# S03.net
KiCad netlist of a schematic drawn in Altium Designer
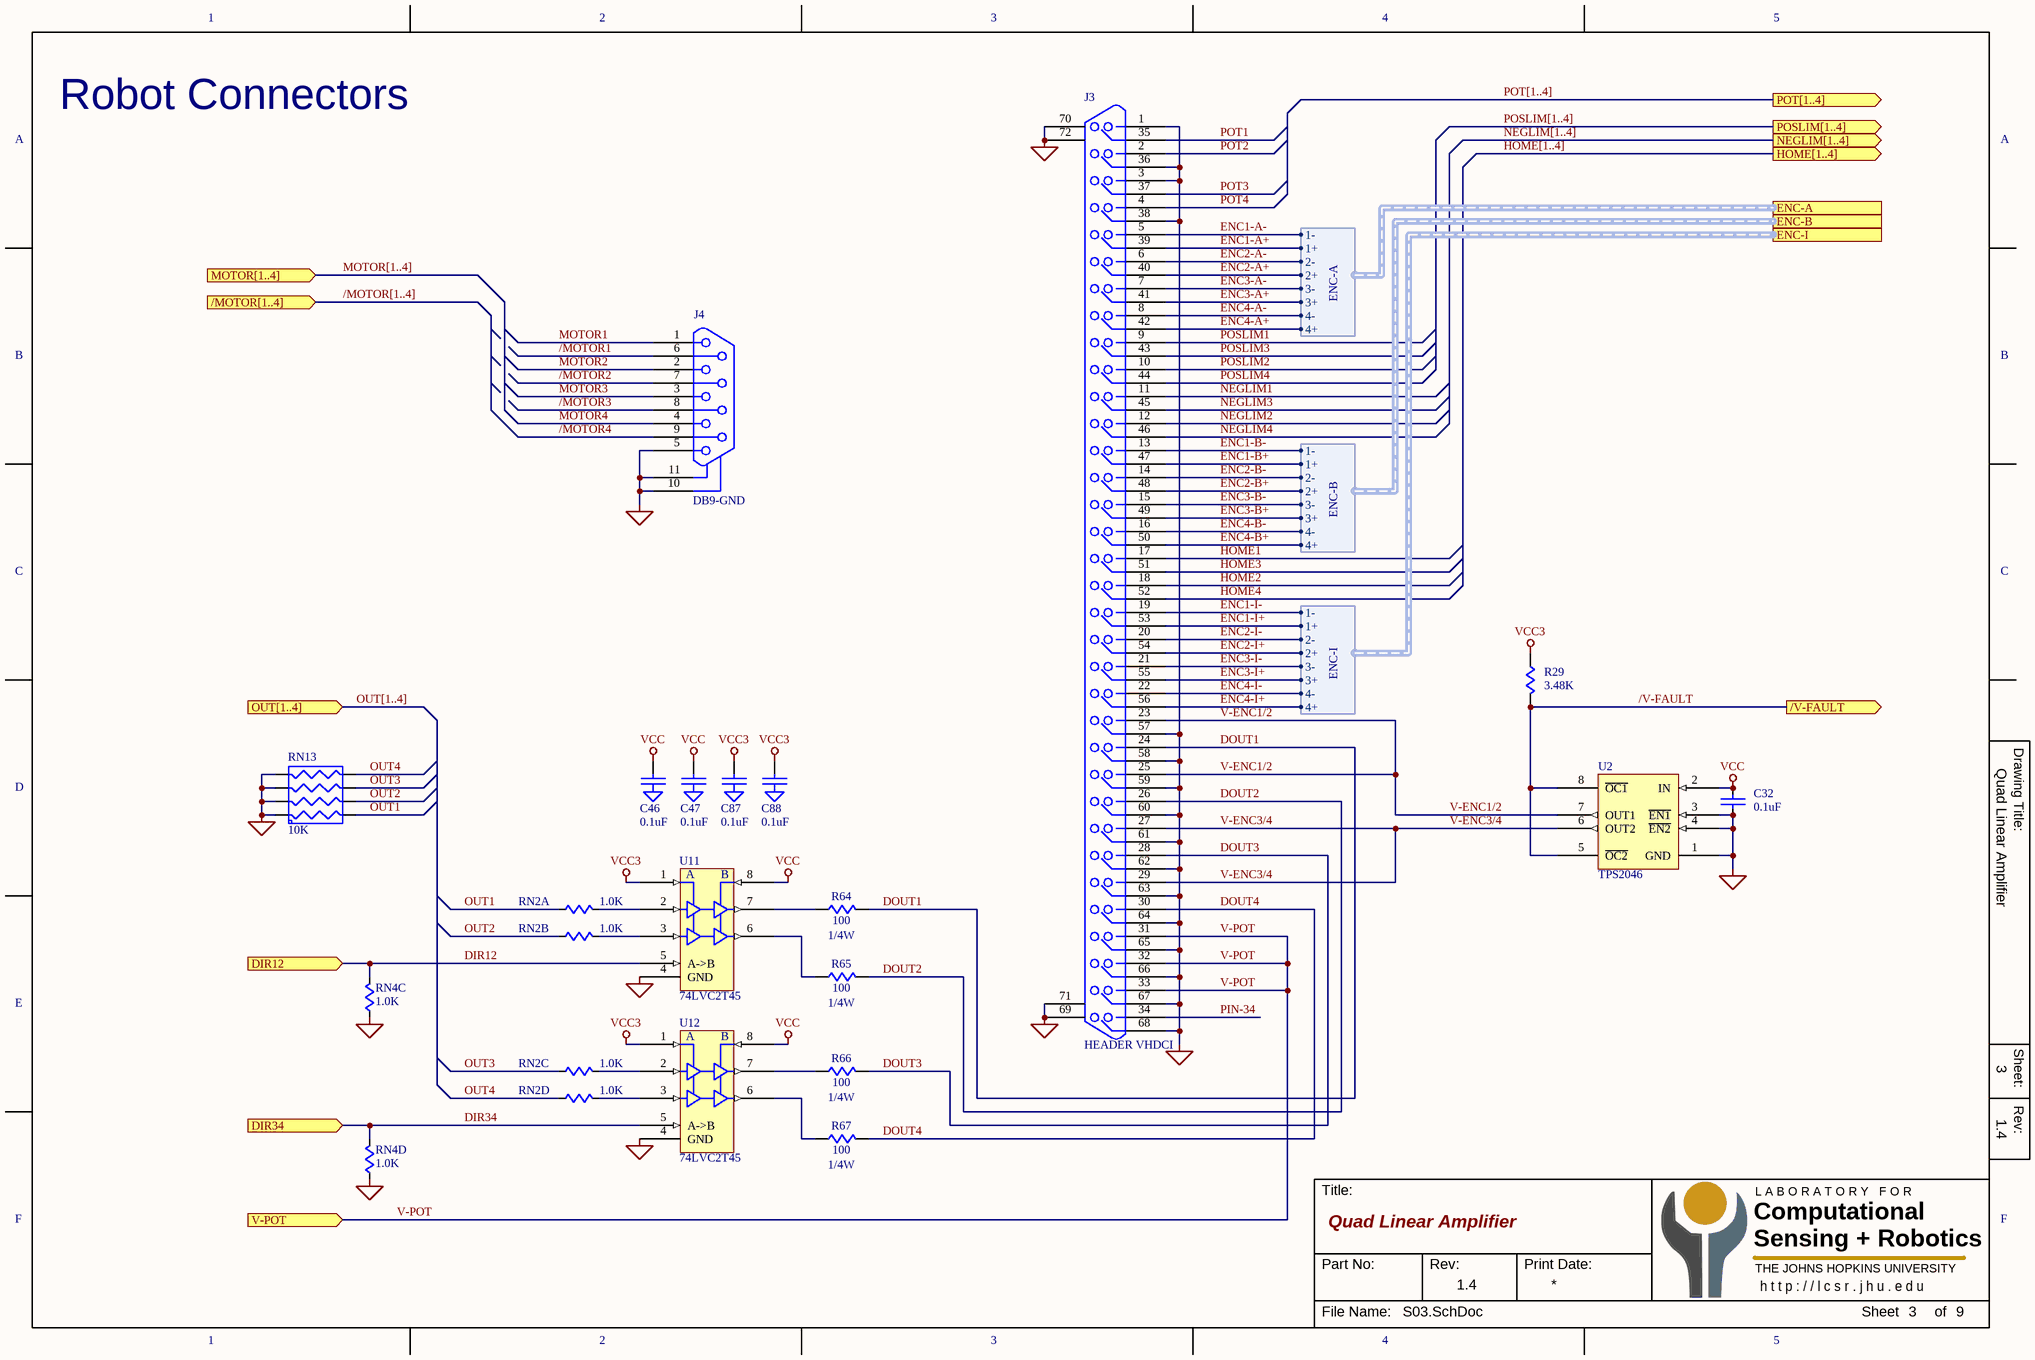
[diagram p0: S03.SchDoc]

(export (version "E")
  (design (tool "Eeschema 10.0.6"))
  (components
    (comp (ref "C32") (value "0.1uF") (footprint "C0603") (libsource (lib "LibJHU") (part "CAP-MINI")))
    (comp (ref "C46") (value "0.1uF") (footprint "C0603") (libsource (lib "LibJHU") (part "CAP-GND")))
    (comp (ref "C47") (value "0.1uF") (footprint "C0603") (libsource (lib "LibJHU") (part "CAP-GND")))
    (comp (ref "C87") (value "0.1uF") (footprint "C0603") (libsource (lib "LibJHU") (part "CAP-GND")))
    (comp (ref "C88") (value "0.1uF") (footprint "C0603") (libsource (lib "LibJHU") (part "CAP-GND")))
    (comp (ref "J3")
      (value "HEADER VHDCI")
      (footprint "CONN-VHDCI")
      (description "Molex Part #71430-0008")
      (libsource (lib "LibJHU") (part "HEADER VHDCI"))
    )
    (comp (ref "J4")
      (value "DB9-GND")
      (footprint "DB9F/RA-545-HDP")
      (libsource (lib "LibJHU") (part "DB9-GND"))
    )
    (comp (ref "R29") (value "3.48K") (footprint "R0603") (libsource (lib "LibJHU") (part "R")))
    (comp (ref "R64")
      (value "100")
      (footprint "R1206")
      (fields (field (name "ALTIUM_UNNAMED_1") "1/4W"))
      (libsource (lib "LibJHU") (part "R"))
    )
    (comp (ref "R65")
      (value "100")
      (footprint "R1206")
      (fields (field (name "ALTIUM_UNNAMED_1") "1/4W"))
      (libsource (lib "LibJHU") (part "R"))
    )
    (comp (ref "R66")
      (value "100")
      (footprint "R1206")
      (fields (field (name "ALTIUM_UNNAMED_1") "1/4W"))
      (libsource (lib "LibJHU") (part "R"))
    )
    (comp (ref "R67")
      (value "100")
      (footprint "R1206")
      (fields (field (name "ALTIUM_UNNAMED_1") "1/4W"))
      (libsource (lib "LibJHU") (part "R"))
    )
    (comp (ref "RN2")
      (value "1.0K")
      (footprint "RN-742C083")
      (libsource (lib "LibJHU") (part "RN-DISC-SM-4X"))
    )
    (comp (ref "RN4")
      (value "1.0K")
      (footprint "RN-742C083")
      (libsource (lib "LibJHU") (part "RN-DISC-SM-4X"))
    )
    (comp (ref "RN13")
      (value "10K")
      (footprint "RN-742C083")
      (libsource (lib "LibJHU") (part "RN-DISC-SM-4"))
    )
    (comp (ref "U2") (value "TPS2046") (footprint "SO-8") (libsource (lib "LibJHU") (part "TPS2046")))
    (comp (ref "U11") (value "74LVC2T45") (footprint "US8-8") (libsource (lib "LibJHU") (part "74LVC2T45")))
    (comp (ref "U12") (value "74LVC2T45") (footprint "US8-8") (libsource (lib "LibJHU") (part "74LVC2T45")))
  )
  (nets
    (net (code "8") (name "/DIR12") (class "Default")
      (node (ref "RN4") (pin "6") (pinfunction "6_6") (pintype "passive"))
      (node (ref "U11") (pin "5") (pinfunction "A->B_5") (pintype "input"))
    )
    (net (code "9") (name "/DIR34") (class "Default")
      (node (ref "RN4") (pin "5") (pinfunction "5_5") (pintype "passive"))
      (node (ref "U12") (pin "5") (pinfunction "A->B_5") (pintype "input"))
    )
    (net (code "10") (name "/DOUT1") (class "Default")
      (node (ref "J3") (pin "24") (pinfunction "24_24") (pintype "passive"))
      (node (ref "R64") (pin "2") (pinfunction "2_2") (pintype "passive"))
    )
    (net (code "11") (name "/DOUT2") (class "Default")
      (node (ref "J3") (pin "26") (pinfunction "26_26") (pintype "passive"))
      (node (ref "R65") (pin "2") (pinfunction "2_2") (pintype "passive"))
    )
    (net (code "12") (name "/DOUT3") (class "Default")
      (node (ref "J3") (pin "28") (pinfunction "28_28") (pintype "passive"))
      (node (ref "R66") (pin "2") (pinfunction "2_2") (pintype "passive"))
    )
    (net (code "13") (name "/DOUT4") (class "Default")
      (node (ref "J3") (pin "30") (pinfunction "30_30") (pintype "passive"))
      (node (ref "R67") (pin "2") (pinfunction "2_2") (pintype "passive"))
    )
    (net (code "14") (name "/ENC1-A+") (class "Default")
      (node (ref "J3") (pin "39") (pinfunction "39_39") (pintype "passive"))
    )
    (net (code "15") (name "/ENC1-A-") (class "Default")
      (node (ref "J3") (pin "5") (pinfunction "5_5") (pintype "passive"))
    )
    (net (code "16") (name "/ENC1-B+") (class "Default")
      (node (ref "J3") (pin "47") (pinfunction "47_47") (pintype "passive"))
    )
    (net (code "17") (name "/ENC1-B-") (class "Default")
      (node (ref "J3") (pin "13") (pinfunction "13_13") (pintype "passive"))
    )
    (net (code "18") (name "/ENC1-I+") (class "Default")
      (node (ref "J3") (pin "53") (pinfunction "53_53") (pintype "passive"))
    )
    (net (code "19") (name "/ENC1-I-") (class "Default")
      (node (ref "J3") (pin "19") (pinfunction "19_19") (pintype "passive"))
    )
    (net (code "20") (name "/ENC2-A+") (class "Default")
      (node (ref "J3") (pin "40") (pinfunction "40_40") (pintype "passive"))
    )
    (net (code "21") (name "/ENC2-A-") (class "Default")
      (node (ref "J3") (pin "6") (pinfunction "6_6") (pintype "passive"))
    )
    (net (code "22") (name "/ENC2-B+") (class "Default")
      (node (ref "J3") (pin "48") (pinfunction "48_48") (pintype "passive"))
    )
    (net (code "23") (name "/ENC2-B-") (class "Default")
      (node (ref "J3") (pin "14") (pinfunction "14_14") (pintype "passive"))
    )
    (net (code "24") (name "/ENC2-I+") (class "Default")
      (node (ref "J3") (pin "54") (pinfunction "54_54") (pintype "passive"))
    )
    (net (code "25") (name "/ENC2-I-") (class "Default")
      (node (ref "J3") (pin "20") (pinfunction "20_20") (pintype "passive"))
    )
    (net (code "26") (name "/ENC3-A+") (class "Default")
      (node (ref "J3") (pin "41") (pinfunction "41_41") (pintype "passive"))
    )
    (net (code "27") (name "/ENC3-A-") (class "Default")
      (node (ref "J3") (pin "7") (pinfunction "7_7") (pintype "passive"))
    )
    (net (code "28") (name "/ENC3-B+") (class "Default")
      (node (ref "J3") (pin "49") (pinfunction "49_49") (pintype "passive"))
    )
    (net (code "29") (name "/ENC3-B-") (class "Default")
      (node (ref "J3") (pin "15") (pinfunction "15_15") (pintype "passive"))
    )
    (net (code "30") (name "/ENC3-I+") (class "Default")
      (node (ref "J3") (pin "55") (pinfunction "55_55") (pintype "passive"))
    )
    (net (code "31") (name "/ENC3-I-") (class "Default")
      (node (ref "J3") (pin "21") (pinfunction "21_21") (pintype "passive"))
    )
    (net (code "32") (name "/ENC4-A+") (class "Default")
      (node (ref "J3") (pin "42") (pinfunction "42_42") (pintype "passive"))
    )
    (net (code "33") (name "/ENC4-A-") (class "Default")
      (node (ref "J3") (pin "8") (pinfunction "8_8") (pintype "passive"))
    )
    (net (code "34") (name "/ENC4-B+") (class "Default")
      (node (ref "J3") (pin "50") (pinfunction "50_50") (pintype "passive"))
    )
    (net (code "35") (name "/ENC4-B-") (class "Default")
      (node (ref "J3") (pin "16") (pinfunction "16_16") (pintype "passive"))
    )
    (net (code "36") (name "/ENC4-I+") (class "Default")
      (node (ref "J3") (pin "56") (pinfunction "56_56") (pintype "passive"))
    )
    (net (code "37") (name "/ENC4-I-") (class "Default")
      (node (ref "J3") (pin "22") (pinfunction "22_22") (pintype "passive"))
    )
    (net (code "38") (name "/HOME1") (class "Default")
      (node (ref "J3") (pin "17") (pinfunction "17_17") (pintype "passive"))
    )
    (net (code "39") (name "/HOME2") (class "Default")
      (node (ref "J3") (pin "18") (pinfunction "18_18") (pintype "passive"))
    )
    (net (code "40") (name "/HOME3") (class "Default")
      (node (ref "J3") (pin "51") (pinfunction "51_51") (pintype "passive"))
    )
    (net (code "41") (name "/HOME4") (class "Default")
      (node (ref "J3") (pin "52") (pinfunction "52_52") (pintype "passive"))
    )
    (net (code "43") (name "/MOTOR1") (class "Default") (node (ref "J4") (pin "1") (pintype "passive")))
    (net (code "44") (name "/MOTOR2") (class "Default") (node (ref "J4") (pin "2") (pintype "passive")))
    (net (code "45") (name "/MOTOR3") (class "Default") (node (ref "J4") (pin "3") (pintype "passive")))
    (net (code "46") (name "/MOTOR4") (class "Default") (node (ref "J4") (pin "4") (pintype "passive")))
    (net (code "48") (name "/NEGLIM1") (class "Default")
      (node (ref "J3") (pin "11") (pinfunction "11_11") (pintype "passive"))
    )
    (net (code "49") (name "/NEGLIM2") (class "Default")
      (node (ref "J3") (pin "12") (pinfunction "12_12") (pintype "passive"))
    )
    (net (code "50") (name "/NEGLIM3") (class "Default")
      (node (ref "J3") (pin "45") (pinfunction "45_45") (pintype "passive"))
    )
    (net (code "51") (name "/NEGLIM4") (class "Default")
      (node (ref "J3") (pin "46") (pinfunction "46_46") (pintype "passive"))
    )
    (net (code "53") (name "/OUT1") (class "Default")
      (node (ref "RN13") (pin "8") (pinfunction "R1.2_8") (pintype "passive"))
      (node (ref "RN2") (pin "1") (pinfunction "1_1") (pintype "passive"))
    )
    (net (code "54") (name "/OUT2") (class "Default")
      (node (ref "RN13") (pin "7") (pinfunction "R2.2_7") (pintype "passive"))
      (node (ref "RN2") (pin "2") (pinfunction "2_2") (pintype "passive"))
    )
    (net (code "55") (name "/OUT3") (class "Default")
      (node (ref "RN13") (pin "6") (pinfunction "R3.2_6") (pintype "passive"))
      (node (ref "RN2") (pin "3") (pinfunction "3_3") (pintype "passive"))
    )
    (net (code "56") (name "/OUT4") (class "Default")
      (node (ref "RN13") (pin "5") (pinfunction "R4.2_5") (pintype "passive"))
      (node (ref "RN2") (pin "4") (pinfunction "4_4") (pintype "passive"))
    )
    (net (code "58") (name "/PIN-34") (class "Default")
      (node (ref "J3") (pin "34") (pinfunction "34_34") (pintype "passive"))
    )
    (net (code "59") (name "/POSLIM1") (class "Default")
      (node (ref "J3") (pin "9") (pinfunction "9_9") (pintype "passive"))
    )
    (net (code "60") (name "/POSLIM2") (class "Default")
      (node (ref "J3") (pin "10") (pinfunction "10_10") (pintype "passive"))
    )
    (net (code "61") (name "/POSLIM3") (class "Default")
      (node (ref "J3") (pin "43") (pinfunction "43_43") (pintype "passive"))
    )
    (net (code "62") (name "/POSLIM4") (class "Default")
      (node (ref "J3") (pin "44") (pinfunction "44_44") (pintype "passive"))
    )
    (net (code "64") (name "/POT1") (class "Default")
      (node (ref "J3") (pin "35") (pinfunction "35_35") (pintype "passive"))
    )
    (net (code "65") (name "/POT2") (class "Default")
      (node (ref "J3") (pin "2") (pinfunction "2_2") (pintype "passive"))
    )
    (net (code "66") (name "/POT3") (class "Default")
      (node (ref "J3") (pin "37") (pinfunction "37_37") (pintype "passive"))
    )
    (net (code "67") (name "/POT4") (class "Default")
      (node (ref "J3") (pin "4") (pinfunction "4_4") (pintype "passive"))
    )
    (net (code "69") (name "/V-ENC1{slash}2") (class "Default")
      (node (ref "J3") (pin "23") (pinfunction "23_23") (pintype "passive"))
      (node (ref "J3") (pin "25") (pinfunction "25_25") (pintype "passive"))
      (node (ref "U2") (pin "7") (pinfunction "OUT1_7") (pintype "output"))
    )
    (net (code "70") (name "/V-ENC3{slash}4") (class "Default")
      (node (ref "J3") (pin "27") (pinfunction "27_27") (pintype "passive"))
      (node (ref "J3") (pin "29") (pinfunction "29_29") (pintype "passive"))
      (node (ref "U2") (pin "6") (pinfunction "OUT2_6") (pintype "output"))
    )
    (net (code "71") (name "/V-POT") (class "Default")
      (node (ref "J3") (pin "31") (pinfunction "31_31") (pintype "passive"))
      (node (ref "J3") (pin "32") (pinfunction "32_32") (pintype "passive"))
      (node (ref "J3") (pin "33") (pinfunction "33_33") (pintype "passive"))
    )
    (net (code "75") (name "/{slash}MOTOR1") (class "Default")
      (node (ref "J4") (pin "6") (pintype "passive"))
    )
    (net (code "76") (name "/{slash}MOTOR2") (class "Default")
      (node (ref "J4") (pin "7") (pintype "passive"))
    )
    (net (code "77") (name "/{slash}MOTOR3") (class "Default")
      (node (ref "J4") (pin "8") (pintype "passive"))
    )
    (net (code "78") (name "/{slash}MOTOR4") (class "Default")
      (node (ref "J4") (pin "9") (pintype "passive"))
    )
    (net (code "80") (name "/{slash}V-FAULT") (class "Default")
      (node (ref "R29") (pin "2") (pinfunction "2_2") (pintype "passive"))
      (node (ref "U2") (pin "5") (pinfunction "OC2_5") (pintype "open_collector"))
      (node (ref "U2") (pin "8") (pinfunction "OC1_8") (pintype "open_collector"))
    )
    (net (code "81") (name "GND") (class "Default")
      (node (ref "C32") (pin "2") (pintype "passive"))
      (node (ref "C46") (pin "2") (pinfunction "GND_2") (pintype "power_in"))
      (node (ref "C47") (pin "2") (pinfunction "GND_2") (pintype "power_in"))
      (node (ref "C87") (pin "2") (pinfunction "GND_2") (pintype "power_in"))
      (node (ref "C88") (pin "2") (pinfunction "GND_2") (pintype "power_in"))
      (node (ref "J3") (pin "1") (pinfunction "1_1") (pintype "passive"))
      (node (ref "J3") (pin "3") (pinfunction "3_3") (pintype "passive"))
      (node (ref "J3") (pin "36") (pinfunction "36_36") (pintype "passive"))
      (node (ref "J3") (pin "38") (pinfunction "38_38") (pintype "passive"))
      (node (ref "J3") (pin "57") (pinfunction "57_57") (pintype "passive"))
      (node (ref "J3") (pin "58") (pinfunction "58_58") (pintype "passive"))
      (node (ref "J3") (pin "59") (pinfunction "59_59") (pintype "passive"))
      (node (ref "J3") (pin "60") (pinfunction "60_60") (pintype "passive"))
      (node (ref "J3") (pin "61") (pinfunction "61_61") (pintype "passive"))
      (node (ref "J3") (pin "62") (pinfunction "62_62") (pintype "passive"))
      (node (ref "J3") (pin "63") (pinfunction "63_63") (pintype "passive"))
      (node (ref "J3") (pin "64") (pinfunction "64_64") (pintype "passive"))
      (node (ref "J3") (pin "65") (pinfunction "65_65") (pintype "passive"))
      (node (ref "J3") (pin "66") (pinfunction "66_66") (pintype "passive"))
      (node (ref "J3") (pin "67") (pinfunction "67_67") (pintype "passive"))
      (node (ref "J3") (pin "68") (pinfunction "68_68") (pintype "passive"))
      (node (ref "J3") (pin "69") (pinfunction "69_69") (pintype "passive"))
      (node (ref "J3") (pin "70") (pinfunction "70_70") (pintype "passive"))
      (node (ref "J3") (pin "71") (pinfunction "71_71") (pintype "passive"))
      (node (ref "J3") (pin "72") (pinfunction "72_72") (pintype "passive"))
      (node (ref "J4") (pin "10") (pinfunction "GND_10") (pintype "power_in"))
      (node (ref "J4") (pin "11") (pinfunction "GND_11") (pintype "power_in"))
      (node (ref "J4") (pin "5") (pintype "passive"))
      (node (ref "RN13") (pin "1") (pinfunction "R1_1") (pintype "passive"))
      (node (ref "RN13") (pin "2") (pinfunction "R2.1_2") (pintype "passive"))
      (node (ref "RN13") (pin "3") (pinfunction "R3.1_3") (pintype "passive"))
      (node (ref "RN13") (pin "4") (pinfunction "R4.1_4") (pintype "passive"))
      (node (ref "RN4") (pin "3") (pinfunction "3_3") (pintype "passive"))
      (node (ref "RN4") (pin "4") (pinfunction "4_4") (pintype "passive"))
      (node (ref "U11") (pin "4") (pinfunction "GND_4") (pintype "power_in"))
      (node (ref "U12") (pin "4") (pinfunction "GND_4") (pintype "power_in"))
      (node (ref "U2") (pin "1") (pinfunction "GND_1") (pintype "power_in"))
      (node (ref "U2") (pin "3") (pinfunction "EN1_3") (pintype "input"))
      (node (ref "U2") (pin "4") (pinfunction "EN2_4") (pintype "input"))
    )
    (net (code "82") (name "Net-(R64-Pad1)") (class "Default")
      (node (ref "R64") (pin "1") (pinfunction "1_1") (pintype "passive"))
      (node (ref "U11") (pin "7") (pinfunction "B_7") (pintype "output"))
    )
    (net (code "83") (name "Net-(R65-Pad1)") (class "Default")
      (node (ref "R65") (pin "1") (pinfunction "1_1") (pintype "passive"))
      (node (ref "U11") (pin "6") (pinfunction "B_6") (pintype "output"))
    )
    (net (code "84") (name "Net-(R66-Pad1)") (class "Default")
      (node (ref "R66") (pin "1") (pinfunction "1_1") (pintype "passive"))
      (node (ref "U12") (pin "7") (pinfunction "B_7") (pintype "output"))
    )
    (net (code "85") (name "Net-(R67-Pad1)") (class "Default")
      (node (ref "R67") (pin "1") (pinfunction "1_1") (pintype "passive"))
      (node (ref "U12") (pin "6") (pinfunction "B_6") (pintype "output"))
    )
    (net (code "86") (name "Net-(RN2-Pad5)") (class "Default")
      (node (ref "RN2") (pin "5") (pinfunction "5_5") (pintype "passive"))
      (node (ref "U12") (pin "3") (pinfunction "A_3") (pintype "input"))
    )
    (net (code "87") (name "Net-(RN2-Pad6)") (class "Default")
      (node (ref "RN2") (pin "6") (pinfunction "6_6") (pintype "passive"))
      (node (ref "U12") (pin "2") (pinfunction "A_2") (pintype "input"))
    )
    (net (code "88") (name "Net-(RN2-Pad7)") (class "Default")
      (node (ref "RN2") (pin "7") (pinfunction "7_7") (pintype "passive"))
      (node (ref "U11") (pin "3") (pinfunction "A_3") (pintype "input"))
    )
    (net (code "89") (name "Net-(RN2-Pad8)") (class "Default")
      (node (ref "RN2") (pin "8") (pinfunction "8_8") (pintype "passive"))
      (node (ref "U11") (pin "2") (pinfunction "A_2") (pintype "input"))
    )
    (net (code "90") (name "VCC") (class "Default")
      (node (ref "C32") (pin "1") (pintype "passive"))
      (node (ref "C46") (pin "1") (pintype "passive"))
      (node (ref "C47") (pin "1") (pintype "passive"))
      (node (ref "U11") (pin "8") (pinfunction "VCCB_8") (pintype "input"))
      (node (ref "U12") (pin "8") (pinfunction "VCCB_8") (pintype "input"))
      (node (ref "U2") (pin "2") (pinfunction "IN_2") (pintype "input"))
    )
    (net (code "91") (name "VCC3") (class "Default")
      (node (ref "C87") (pin "1") (pintype "passive"))
      (node (ref "C88") (pin "1") (pintype "passive"))
      (node (ref "R29") (pin "1") (pinfunction "1_1") (pintype "passive"))
      (node (ref "U11") (pin "1") (pinfunction "VCCA_1") (pintype "input"))
      (node (ref "U12") (pin "1") (pinfunction "VCCA_1") (pintype "input"))
    )
  )
)
